# MP2637.net
KiCad netlist of a schematic drawn in Altium Designer
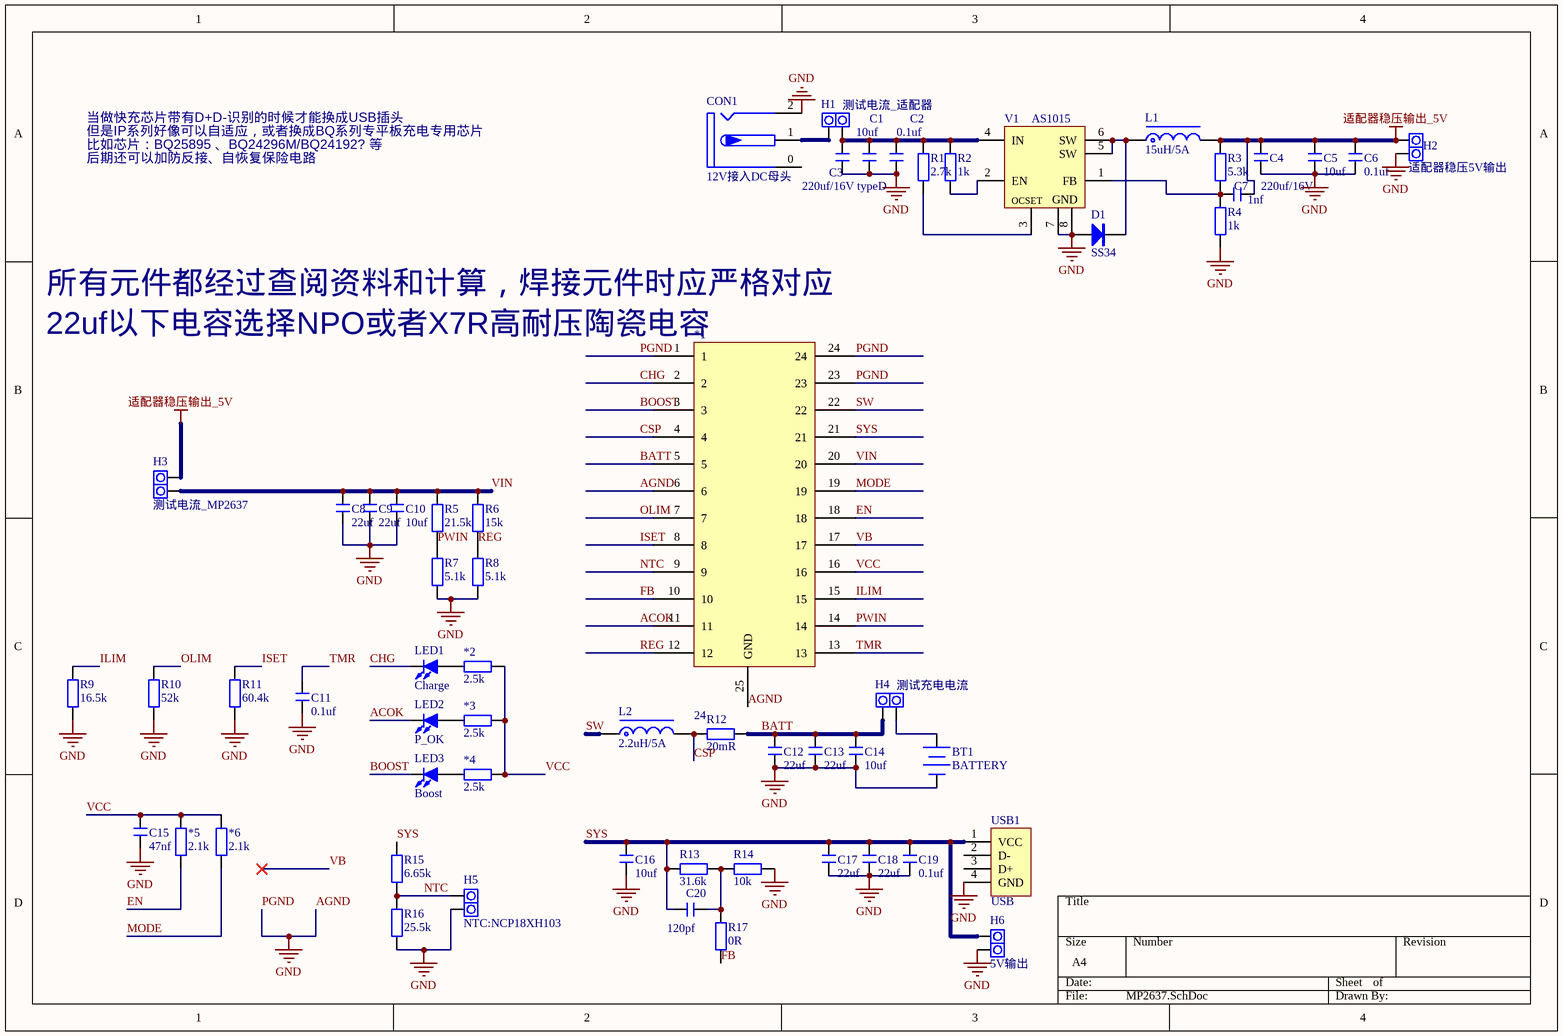
[diagram p0: MP2637.SchDoc]

(export (version "E")
  (design (tool "Eeschema 10.0.6"))
  (components
    (comp (ref "*1") (value "24") (footprint "QFN24 4x4_M") (libsource (lib "IC_temp") (part "24")))
    (comp (ref "*2")
      (value "2.5k")
      (footprint "R 0805_M")
      (description "贴片电阻")
      (libsource (lib "3.1   - 电阻-电容-电感") (part "R"))
    )
    (comp (ref "*3")
      (value "2.5k")
      (footprint "R 0805_M")
      (description "贴片电阻")
      (libsource (lib "3.1   - 电阻-电容-电感") (part "R"))
    )
    (comp (ref "*4")
      (value "2.5k")
      (footprint "R 0805_M")
      (description "贴片电阻")
      (libsource (lib "3.1   - 电阻-电容-电感") (part "R"))
    )
    (comp (ref "*5")
      (value "2.1k")
      (footprint "R 0805_M")
      (description "贴片电阻")
      (libsource (lib "3.1   - 电阻-电容-电感") (part "R"))
    )
    (comp (ref "*6")
      (value "2.1k")
      (footprint "R 0805_M")
      (description "贴片电阻")
      (libsource (lib "3.1   - 电阻-电容-电感") (part "R"))
    )
    (comp (ref "BT1")
      (value "BATTERY")
      (footprint "BAT-2")
      (description "Multicell Battery")
      (fields (field (name "PUBLISHER") "Altium Limited"))
      (libsource (lib "rest") (part "BATTERY"))
    )
    (comp (ref "C1")
      (value "10uf")
      (footprint "C 0805_M")
      (description "无极性贴片电容")
      (libsource (lib "3.1   - 电阻-电容-电感") (part "C"))
    )
    (comp (ref "C2")
      (value "0.1uf")
      (footprint "C 0805_M")
      (description "无极性贴片电容")
      (libsource (lib "3.1   - 电阻-电容-电感") (part "C"))
    )
    (comp (ref "C3")
      (value "220uf/16V typeD")
      (footprint "CD D(7343)")
      (description "无极性贴片电容")
      (libsource (lib "3.1   - 电阻-电容-电感") (part "C"))
    )
    (comp (ref "C4")
      (value "220uf/16V")
      (footprint "CD D(7343)")
      (description "无极性贴片电容")
      (libsource (lib "3.1   - 电阻-电容-电感") (part "C"))
    )
    (comp (ref "C5")
      (value "10uf")
      (footprint "C 0805_M")
      (description "无极性贴片电容")
      (libsource (lib "3.1   - 电阻-电容-电感") (part "C"))
    )
    (comp (ref "C6")
      (value "0.1uf")
      (footprint "C 0805_M")
      (description "无极性贴片电容")
      (libsource (lib "3.1   - 电阻-电容-电感") (part "C"))
    )
    (comp (ref "C7")
      (value "1nf")
      (footprint "C 0805_M")
      (description "无极性贴片电容")
      (libsource (lib "3.1   - 电阻-电容-电感") (part "C"))
    )
    (comp (ref "C8")
      (value "22uf")
      (footprint "C 0805_M")
      (description "无极性贴片电容")
      (libsource (lib "3.1   - 电阻-电容-电感") (part "C"))
    )
    (comp (ref "C9")
      (value "22uf")
      (footprint "C 0805_M")
      (description "无极性贴片电容")
      (libsource (lib "3.1   - 电阻-电容-电感") (part "C"))
    )
    (comp (ref "C10")
      (value "10uf")
      (footprint "C 0805_M")
      (description "无极性贴片电容")
      (libsource (lib "3.1   - 电阻-电容-电感") (part "C"))
    )
    (comp (ref "C11")
      (value "0.1uf")
      (footprint "C 0805_M")
      (description "无极性贴片电容")
      (libsource (lib "3.1   - 电阻-电容-电感") (part "C"))
    )
    (comp (ref "C12")
      (value "22uf")
      (footprint "C 0805_M")
      (description "无极性贴片电容")
      (libsource (lib "3.1   - 电阻-电容-电感") (part "C"))
    )
    (comp (ref "C13")
      (value "22uf")
      (footprint "C 0805_M")
      (description "无极性贴片电容")
      (libsource (lib "3.1   - 电阻-电容-电感") (part "C"))
    )
    (comp (ref "C14")
      (value "10uf")
      (footprint "C 0805_M")
      (description "无极性贴片电容")
      (libsource (lib "3.1   - 电阻-电容-电感") (part "C"))
    )
    (comp (ref "C15")
      (value "47nf")
      (footprint "C 0805_M")
      (description "无极性贴片电容")
      (libsource (lib "3.1   - 电阻-电容-电感") (part "C"))
    )
    (comp (ref "C16")
      (value "10uf")
      (footprint "C 0805_M")
      (description "无极性贴片电容")
      (libsource (lib "3.1   - 电阻-电容-电感") (part "C"))
    )
    (comp (ref "C17")
      (value "22uf")
      (footprint "C 0805_M")
      (description "无极性贴片电容")
      (libsource (lib "3.1   - 电阻-电容-电感") (part "C"))
    )
    (comp (ref "C18")
      (value "22uf")
      (footprint "C 0805_M")
      (description "无极性贴片电容")
      (libsource (lib "3.1   - 电阻-电容-电感") (part "C"))
    )
    (comp (ref "C19")
      (value "0.1uf")
      (footprint "C 0805_M")
      (description "无极性贴片电容")
      (libsource (lib "3.1   - 电阻-电容-电感") (part "C"))
    )
    (comp (ref "C20")
      (value "120pf")
      (footprint "C 0805_M")
      (description "无极性贴片电容")
      (libsource (lib "3.1   - 电阻-电容-电感") (part "C"))
    )
    (comp (ref "CON1")
      (value "12V接入DC母头")
      (footprint "DC-005P")
      (description "带屏蔽DC电源接口")
      (libsource (lib "4.1   - 接口类") (part "DC-005P"))
    )
    (comp (ref "D1")
      (value "SS34")
      (footprint "SMA")
      (description "肖特基二极管")
      (libsource (lib "8.1   - 二极管-整流桥") (part "SS34"))
    )
    (comp (ref "H1")
      (value "测试电流_适配器")
      (footprint "PAD2-2.54")
      (description "引线焊盘")
      (libsource (lib "15.1 - 未分类器件") (part "PAD2"))
    )
    (comp (ref "H2")
      (value "适配器稳压5V输出")
      (footprint "PAD2-2.54")
      (description "引线焊盘")
      (libsource (lib "15.1 - 未分类器件") (part "PAD2"))
    )
    (comp (ref "H3")
      (value "测试电流_MP2637")
      (footprint "PAD2-2.54")
      (description "引线焊盘")
      (libsource (lib "15.1 - 未分类器件") (part "PAD2"))
    )
    (comp (ref "H4")
      (value "测试充电电流")
      (footprint "PAD2-2.54")
      (description "引线焊盘")
      (libsource (lib "15.1 - 未分类器件") (part "PAD2"))
    )
    (comp (ref "H5")
      (value "NTC:NCP18XH103")
      (footprint "PAD2-2.54")
      (description "引线焊盘")
      (libsource (lib "15.1 - 未分类器件") (part "PAD2"))
    )
    (comp (ref "H6")
      (value "5V输出")
      (footprint "PAD2-2.54")
      (description "引线焊盘")
      (libsource (lib "15.1 - 未分类器件") (part "PAD2"))
    )
    (comp (ref "L1")
      (value "15uH/5A")
      (footprint "L-SMD-0630")
      (description "功率屏蔽电感")
      (libsource (lib "3.1   - 电阻-电容-电感") (part "L-CDRH"))
    )
    (comp (ref "L2")
      (value "2.2uH/5A")
      (footprint "L-SMD-0630")
      (description "功率屏蔽电感")
      (libsource (lib "3.1   - 电阻-电容-电感") (part "L-CDRH"))
    )
    (comp (ref "LED1")
      (value "Charge")
      (footprint "LED 0805G")
      (description "贴片LED")
      (libsource (lib "9.1   - LED") (part "LED-SMD"))
    )
    (comp (ref "LED2")
      (value "P_OK")
      (footprint "LED 0805G")
      (description "贴片LED")
      (libsource (lib "9.1   - LED") (part "LED-SMD"))
    )
    (comp (ref "LED3")
      (value "Boost")
      (footprint "LED 0805G")
      (description "贴片LED")
      (libsource (lib "9.1   - LED") (part "LED-SMD"))
    )
    (comp (ref "R1")
      (value "2.7k")
      (footprint "R 0805_M")
      (description "贴片电阻")
      (libsource (lib "3.1   - 电阻-电容-电感") (part "R"))
    )
    (comp (ref "R2")
      (value "1k")
      (footprint "R 0805_M")
      (description "贴片电阻")
      (libsource (lib "3.1   - 电阻-电容-电感") (part "R"))
    )
    (comp (ref "R3")
      (value "5.3k")
      (footprint "R 0805_M")
      (description "贴片电阻")
      (libsource (lib "3.1   - 电阻-电容-电感") (part "R"))
    )
    (comp (ref "R4")
      (value "1k")
      (footprint "R 0805_M")
      (description "贴片电阻")
      (libsource (lib "3.1   - 电阻-电容-电感") (part "R"))
    )
    (comp (ref "R5")
      (value "21.5k")
      (footprint "R 0805_M")
      (description "贴片电阻")
      (libsource (lib "3.1   - 电阻-电容-电感") (part "R"))
    )
    (comp (ref "R6")
      (value "15k")
      (footprint "R 0805_M")
      (description "贴片电阻")
      (libsource (lib "3.1   - 电阻-电容-电感") (part "R"))
    )
    (comp (ref "R7")
      (value "5.1k")
      (footprint "R 0805_M")
      (description "贴片电阻")
      (libsource (lib "3.1   - 电阻-电容-电感") (part "R"))
    )
    (comp (ref "R8")
      (value "5.1k")
      (footprint "R 0805_M")
      (description "贴片电阻")
      (libsource (lib "3.1   - 电阻-电容-电感") (part "R"))
    )
    (comp (ref "R9")
      (value "16.5k")
      (footprint "R 0805_M")
      (description "贴片电阻")
      (libsource (lib "3.1   - 电阻-电容-电感") (part "R"))
    )
    (comp (ref "R10")
      (value "52k")
      (footprint "R 0805_M")
      (description "贴片电阻")
      (libsource (lib "3.1   - 电阻-电容-电感") (part "R"))
    )
    (comp (ref "R11")
      (value "60.4k")
      (footprint "R 0805_M")
      (description "贴片电阻")
      (libsource (lib "3.1   - 电阻-电容-电感") (part "R"))
    )
    (comp (ref "R12")
      (value "20mR")
      (footprint "R 2512-HP_L")
      (description "贴片电阻")
      (libsource (lib "3.1   - 电阻-电容-电感") (part "R"))
    )
    (comp (ref "R13")
      (value "31.6k")
      (footprint "R 0805_M")
      (description "贴片电阻")
      (libsource (lib "3.1   - 电阻-电容-电感") (part "R"))
    )
    (comp (ref "R14")
      (value "10k")
      (footprint "R 0805_M")
      (description "贴片电阻")
      (libsource (lib "3.1   - 电阻-电容-电感") (part "R"))
    )
    (comp (ref "R15")
      (value "6.65k")
      (footprint "R 0805_M")
      (description "贴片电阻")
      (libsource (lib "3.1   - 电阻-电容-电感") (part "R"))
    )
    (comp (ref "R16")
      (value "25.5k")
      (footprint "R 0805_M")
      (description "贴片电阻")
      (libsource (lib "3.1   - 电阻-电容-电感") (part "R"))
    )
    (comp (ref "R17")
      (value "0R")
      (footprint "R 0805_M")
      (description "贴片电阻")
      (libsource (lib "3.1   - 电阻-电容-电感") (part "R"))
    )
    (comp (ref "USB1")
      (value "USB")
      (footprint "USB-A/S_A")
      (description "USB-A型母接口")
      (libsource (lib "4.1   - 接口类") (part "USB-A/S"))
    )
    (comp (ref "V1")
      (value "AS1015")
      (footprint "SOP8_N")
      (description "可调升压芯片")
      (libsource (lib "1.3   - 电源类芯片") (part "AS1015"))
    )
  )
  (nets
    (net (code "1") (name "/ACOK") (class "Default")
      (node (ref "*1") (pin "11") (pinfunction "11_11") (pintype "passive"))
      (node (ref "LED2") (pin "2") (pinfunction "K_2") (pintype "passive"))
    )
    (net (code "2") (name "/BATT") (class "Default")
      (node (ref "*1") (pin "5") (pinfunction "5_5") (pintype "passive"))
      (node (ref "C12") (pin "2") (pinfunction "2_2") (pintype "passive"))
      (node (ref "C13") (pin "2") (pinfunction "2_2") (pintype "passive"))
      (node (ref "C14") (pin "2") (pinfunction "2_2") (pintype "passive"))
      (node (ref "H4") (pin "1") (pinfunction "1_1") (pintype "passive"))
      (node (ref "R12") (pin "2") (pinfunction "2_2") (pintype "passive"))
    )
    (net (code "3") (name "/BOOST") (class "Default")
      (node (ref "*1") (pin "3") (pinfunction "3_3") (pintype "passive"))
      (node (ref "LED3") (pin "2") (pinfunction "K_2") (pintype "passive"))
    )
    (net (code "4") (name "/CHG") (class "Default")
      (node (ref "*1") (pin "2") (pinfunction "2_2") (pintype "passive"))
      (node (ref "LED1") (pin "2") (pinfunction "K_2") (pintype "passive"))
    )
    (net (code "5") (name "/CSP") (class "Default")
      (node (ref "*1") (pin "4") (pinfunction "4_4") (pintype "passive"))
      (node (ref "L2") (pin "2") (pinfunction "2_2") (pintype "passive"))
      (node (ref "R12") (pin "1") (pinfunction "1_1") (pintype "passive"))
    )
    (net (code "6") (name "/EN") (class "Default")
      (node (ref "*1") (pin "18") (pinfunction "18_18") (pintype "passive"))
      (node (ref "*5") (pin "2") (pinfunction "2_2") (pintype "passive"))
    )
    (net (code "7") (name "/FB") (class "Default")
      (node (ref "*1") (pin "10") (pinfunction "10_10") (pintype "passive"))
      (node (ref "R17") (pin "1") (pinfunction "1_1") (pintype "passive"))
    )
    (net (code "8") (name "/ILIM") (class "Default")
      (node (ref "*1") (pin "15") (pinfunction "15_15") (pintype "passive"))
      (node (ref "R9") (pin "1") (pinfunction "1_1") (pintype "passive"))
    )
    (net (code "9") (name "/ISET") (class "Default")
      (node (ref "*1") (pin "8") (pinfunction "8_8") (pintype "passive"))
      (node (ref "R11") (pin "2") (pinfunction "2_2") (pintype "passive"))
    )
    (net (code "10") (name "/MODE") (class "Default")
      (node (ref "*1") (pin "19") (pinfunction "19_19") (pintype "passive"))
      (node (ref "*6") (pin "2") (pinfunction "2_2") (pintype "passive"))
    )
    (net (code "11") (name "/NTC") (class "Default")
      (node (ref "*1") (pin "9") (pinfunction "9_9") (pintype "passive"))
      (node (ref "H5") (pin "1") (pinfunction "1_1") (pintype "passive"))
      (node (ref "R15") (pin "2") (pinfunction "2_2") (pintype "passive"))
      (node (ref "R16") (pin "1") (pinfunction "1_1") (pintype "passive"))
    )
    (net (code "12") (name "/OLIM") (class "Default")
      (node (ref "*1") (pin "7") (pinfunction "7_7") (pintype "passive"))
      (node (ref "R10") (pin "2") (pinfunction "2_2") (pintype "passive"))
    )
    (net (code "13") (name "/PWIN") (class "Default")
      (node (ref "*1") (pin "14") (pinfunction "14_14") (pintype "passive"))
      (node (ref "R5") (pin "2") (pinfunction "2_2") (pintype "passive"))
      (node (ref "R7") (pin "1") (pinfunction "1_1") (pintype "passive"))
    )
    (net (code "14") (name "/REG") (class "Default")
      (node (ref "*1") (pin "12") (pinfunction "12_12") (pintype "passive"))
      (node (ref "R6") (pin "2") (pinfunction "2_2") (pintype "passive"))
      (node (ref "R8") (pin "1") (pinfunction "1_1") (pintype "passive"))
    )
    (net (code "15") (name "/SW") (class "Default")
      (node (ref "*1") (pin "22") (pinfunction "22_22") (pintype "passive"))
      (node (ref "L2") (pin "1") (pinfunction "1_1") (pintype "passive"))
    )
    (net (code "16") (name "/SYS") (class "Default")
      (node (ref "*1") (pin "21") (pinfunction "21_21") (pintype "passive"))
      (node (ref "C16") (pin "2") (pinfunction "2_2") (pintype "passive"))
      (node (ref "C17") (pin "2") (pinfunction "2_2") (pintype "passive"))
      (node (ref "C18") (pin "2") (pinfunction "2_2") (pintype "passive"))
      (node (ref "C19") (pin "2") (pinfunction "2_2") (pintype "passive"))
      (node (ref "C20") (pin "1") (pinfunction "1_1") (pintype "passive"))
      (node (ref "H6") (pin "1") (pinfunction "1_1") (pintype "passive"))
      (node (ref "R13") (pin "1") (pinfunction "1_1") (pintype "passive"))
      (node (ref "R15") (pin "1") (pinfunction "1_1") (pintype "passive"))
      (node (ref "USB1") (pin "1") (pinfunction "VCC_1") (pintype "passive"))
    )
    (net (code "17") (name "/TMR") (class "Default")
      (node (ref "*1") (pin "13") (pinfunction "13_13") (pintype "passive"))
      (node (ref "C11") (pin "2") (pinfunction "2_2") (pintype "passive"))
    )
    (net (code "18") (name "/VB") (class "Default")
      (node (ref "*1") (pin "17") (pinfunction "17_17") (pintype "passive"))
    )
    (net (code "19") (name "/VCC") (class "Default")
      (node (ref "*1") (pin "16") (pinfunction "16_16") (pintype "passive"))
      (node (ref "*2") (pin "2") (pinfunction "2_2") (pintype "passive"))
      (node (ref "*3") (pin "2") (pinfunction "2_2") (pintype "passive"))
      (node (ref "*4") (pin "2") (pinfunction "2_2") (pintype "passive"))
      (node (ref "*5") (pin "1") (pinfunction "1_1") (pintype "passive"))
      (node (ref "*6") (pin "1") (pinfunction "1_1") (pintype "passive"))
      (node (ref "C15") (pin "2") (pinfunction "2_2") (pintype "passive"))
    )
    (net (code "20") (name "/VIN") (class "Default")
      (node (ref "*1") (pin "20") (pinfunction "20_20") (pintype "passive"))
      (node (ref "C10") (pin "2") (pinfunction "2_2") (pintype "passive"))
      (node (ref "C8") (pin "2") (pinfunction "2_2") (pintype "passive"))
      (node (ref "C9") (pin "2") (pinfunction "2_2") (pintype "passive"))
      (node (ref "H3") (pin "1") (pinfunction "1_1") (pintype "passive"))
      (node (ref "R5") (pin "1") (pinfunction "1_1") (pintype "passive"))
      (node (ref "R6") (pin "1") (pinfunction "1_1") (pintype "passive"))
    )
    (net (code "21") (name "GND") (class "Default")
      (node (ref "*1") (pin "1") (pinfunction "1_1") (pintype "passive"))
      (node (ref "*1") (pin "23") (pinfunction "23_23") (pintype "passive"))
      (node (ref "*1") (pin "24") (pinfunction "24_24") (pintype "passive"))
      (node (ref "*1") (pin "25") (pinfunction "GND_25") (pintype "passive"))
      (node (ref "*1") (pin "6") (pinfunction "6_6") (pintype "passive"))
      (node (ref "BT1") (pin "2") (pinfunction "-_2") (pintype "passive"))
      (node (ref "C1") (pin "1") (pinfunction "1_1") (pintype "passive"))
      (node (ref "C10") (pin "1") (pinfunction "1_1") (pintype "passive"))
      (node (ref "C11") (pin "1") (pinfunction "1_1") (pintype "passive"))
      (node (ref "C12") (pin "1") (pinfunction "1_1") (pintype "passive"))
      (node (ref "C13") (pin "1") (pinfunction "1_1") (pintype "passive"))
      (node (ref "C14") (pin "1") (pinfunction "1_1") (pintype "passive"))
      (node (ref "C15") (pin "1") (pinfunction "1_1") (pintype "passive"))
      (node (ref "C16") (pin "1") (pinfunction "1_1") (pintype "passive"))
      (node (ref "C17") (pin "1") (pinfunction "1_1") (pintype "passive"))
      (node (ref "C18") (pin "1") (pinfunction "1_1") (pintype "passive"))
      (node (ref "C19") (pin "1") (pinfunction "1_1") (pintype "passive"))
      (node (ref "C2") (pin "1") (pinfunction "1_1") (pintype "passive"))
      (node (ref "C3") (pin "1") (pinfunction "1_1") (pintype "passive"))
      (node (ref "C4") (pin "1") (pinfunction "1_1") (pintype "passive"))
      (node (ref "C5") (pin "1") (pinfunction "1_1") (pintype "passive"))
      (node (ref "C6") (pin "1") (pinfunction "1_1") (pintype "passive"))
      (node (ref "C8") (pin "1") (pinfunction "1_1") (pintype "passive"))
      (node (ref "C9") (pin "1") (pinfunction "1_1") (pintype "passive"))
      (node (ref "CON1") (pin "2") (pintype "power_in"))
      (node (ref "D1") (pin "1") (pinfunction "A_1") (pintype "passive"))
      (node (ref "H2") (pin "2") (pinfunction "2_2") (pintype "passive"))
      (node (ref "H5") (pin "2") (pinfunction "2_2") (pintype "passive"))
      (node (ref "H6") (pin "2") (pinfunction "2_2") (pintype "passive"))
      (node (ref "R10") (pin "1") (pinfunction "1_1") (pintype "passive"))
      (node (ref "R11") (pin "1") (pinfunction "1_1") (pintype "passive"))
      (node (ref "R14") (pin "2") (pinfunction "2_2") (pintype "passive"))
      (node (ref "R16") (pin "2") (pinfunction "2_2") (pintype "passive"))
      (node (ref "R4") (pin "2") (pinfunction "2_2") (pintype "passive"))
      (node (ref "R7") (pin "2") (pinfunction "2_2") (pintype "passive"))
      (node (ref "R8") (pin "2") (pinfunction "2_2") (pintype "passive"))
      (node (ref "R9") (pin "2") (pinfunction "2_2") (pintype "passive"))
      (node (ref "USB1") (pin "4") (pinfunction "GND_4") (pintype "passive"))
      (node (ref "V1") (pin "7") (pinfunction "GND_7") (pintype "power_in"))
      (node (ref "V1") (pin "8") (pinfunction "GND_8") (pintype "power_in"))
    )
    (net (code "22") (name "Net-(BT1-+)") (class "Default")
      (node (ref "BT1") (pin "1") (pinfunction "+_1") (pintype "passive"))
      (node (ref "H4") (pin "2") (pinfunction "2_2") (pintype "passive"))
    )
    (net (code "23") (name "Net-(C20-Pad2)") (class "Default")
      (node (ref "C20") (pin "2") (pinfunction "2_2") (pintype "passive"))
      (node (ref "R13") (pin "2") (pinfunction "2_2") (pintype "passive"))
      (node (ref "R14") (pin "1") (pinfunction "1_1") (pintype "passive"))
      (node (ref "R17") (pin "2") (pinfunction "2_2") (pintype "passive"))
    )
    (net (code "24") (name "Net-(CON1-Pad1)") (class "Default")
      (node (ref "CON1") (pin "1") (pintype "power_in"))
      (node (ref "H1") (pin "1") (pinfunction "1_1") (pintype "passive"))
    )
    (net (code "25") (name "Net-(D1-K)") (class "Default")
      (node (ref "D1") (pin "2") (pinfunction "K_2") (pintype "passive"))
      (node (ref "L1") (pin "1") (pinfunction "1_1") (pintype "passive"))
      (node (ref "V1") (pin "5") (pinfunction "SW_5") (pintype "power_in"))
      (node (ref "V1") (pin "6") (pinfunction "SW_6") (pintype "power_in"))
    )
    (net (code "26") (name "Net-(LED1-A)") (class "Default")
      (node (ref "*2") (pin "1") (pinfunction "1_1") (pintype "passive"))
      (node (ref "LED1") (pin "1") (pinfunction "A_1") (pintype "passive"))
    )
    (net (code "27") (name "Net-(LED2-A)") (class "Default")
      (node (ref "*3") (pin "1") (pinfunction "1_1") (pintype "passive"))
      (node (ref "LED2") (pin "1") (pinfunction "A_1") (pintype "passive"))
    )
    (net (code "28") (name "Net-(LED3-A)") (class "Default")
      (node (ref "*4") (pin "1") (pinfunction "1_1") (pintype "passive"))
      (node (ref "LED3") (pin "1") (pinfunction "A_1") (pintype "passive"))
    )
    (net (code "29") (name "Net-(V1-EN)") (class "Default")
      (node (ref "R2") (pin "2") (pinfunction "2_2") (pintype "passive"))
      (node (ref "V1") (pin "2") (pinfunction "EN_2") (pintype "power_in"))
    )
    (net (code "30") (name "Net-(V1-FB)") (class "Default")
      (node (ref "C7") (pin "2") (pinfunction "2_2") (pintype "passive"))
      (node (ref "R3") (pin "2") (pinfunction "2_2") (pintype "passive"))
      (node (ref "R4") (pin "1") (pinfunction "1_1") (pintype "passive"))
      (node (ref "V1") (pin "1") (pinfunction "FB_1") (pintype "power_in"))
    )
    (net (code "31") (name "Net-(V1-IN)") (class "Default")
      (node (ref "C1") (pin "2") (pinfunction "2_2") (pintype "passive"))
      (node (ref "C2") (pin "2") (pinfunction "2_2") (pintype "passive"))
      (node (ref "C3") (pin "2") (pinfunction "2_2") (pintype "passive"))
      (node (ref "H1") (pin "2") (pinfunction "2_2") (pintype "passive"))
      (node (ref "R1") (pin "1") (pinfunction "1_1") (pintype "passive"))
      (node (ref "R2") (pin "1") (pinfunction "1_1") (pintype "passive"))
      (node (ref "V1") (pin "4") (pinfunction "IN_4") (pintype "power_in"))
    )
    (net (code "32") (name "Net-(V1-OCSET)") (class "Default")
      (node (ref "R1") (pin "2") (pinfunction "2_2") (pintype "passive"))
      (node (ref "V1") (pin "3") (pinfunction "OCSET_3") (pintype "power_in"))
    )
    (net (code "33") (name "unconnected-(CON1-Pad0)") (class "Default")
      (node (ref "CON1") (pin "0") (pintype "power_in"))
    )
    (net (code "34") (name "unconnected-(USB1-D+-Pad3)") (class "Default")
      (node (ref "USB1") (pin "3") (pinfunction "D+_3") (pintype "passive"))
    )
    (net (code "35") (name "unconnected-(USB1-D--Pad2)") (class "Default")
      (node (ref "USB1") (pin "2") (pinfunction "D-_2") (pintype "passive"))
    )
    (net (code "36") (name "适配器稳压输出_5V") (class "Default")
      (node (ref "C4") (pin "2") (pinfunction "2_2") (pintype "passive"))
      (node (ref "C5") (pin "2") (pinfunction "2_2") (pintype "passive"))
      (node (ref "C6") (pin "2") (pinfunction "2_2") (pintype "passive"))
      (node (ref "C7") (pin "1") (pinfunction "1_1") (pintype "passive"))
      (node (ref "H2") (pin "1") (pinfunction "1_1") (pintype "passive"))
      (node (ref "H3") (pin "2") (pinfunction "2_2") (pintype "passive"))
      (node (ref "L1") (pin "2") (pinfunction "2_2") (pintype "passive"))
      (node (ref "R3") (pin "1") (pinfunction "1_1") (pintype "passive"))
    )
  )
)
